# Thermocouple.net
KiCad netlist of a schematic drawn in EAGLE
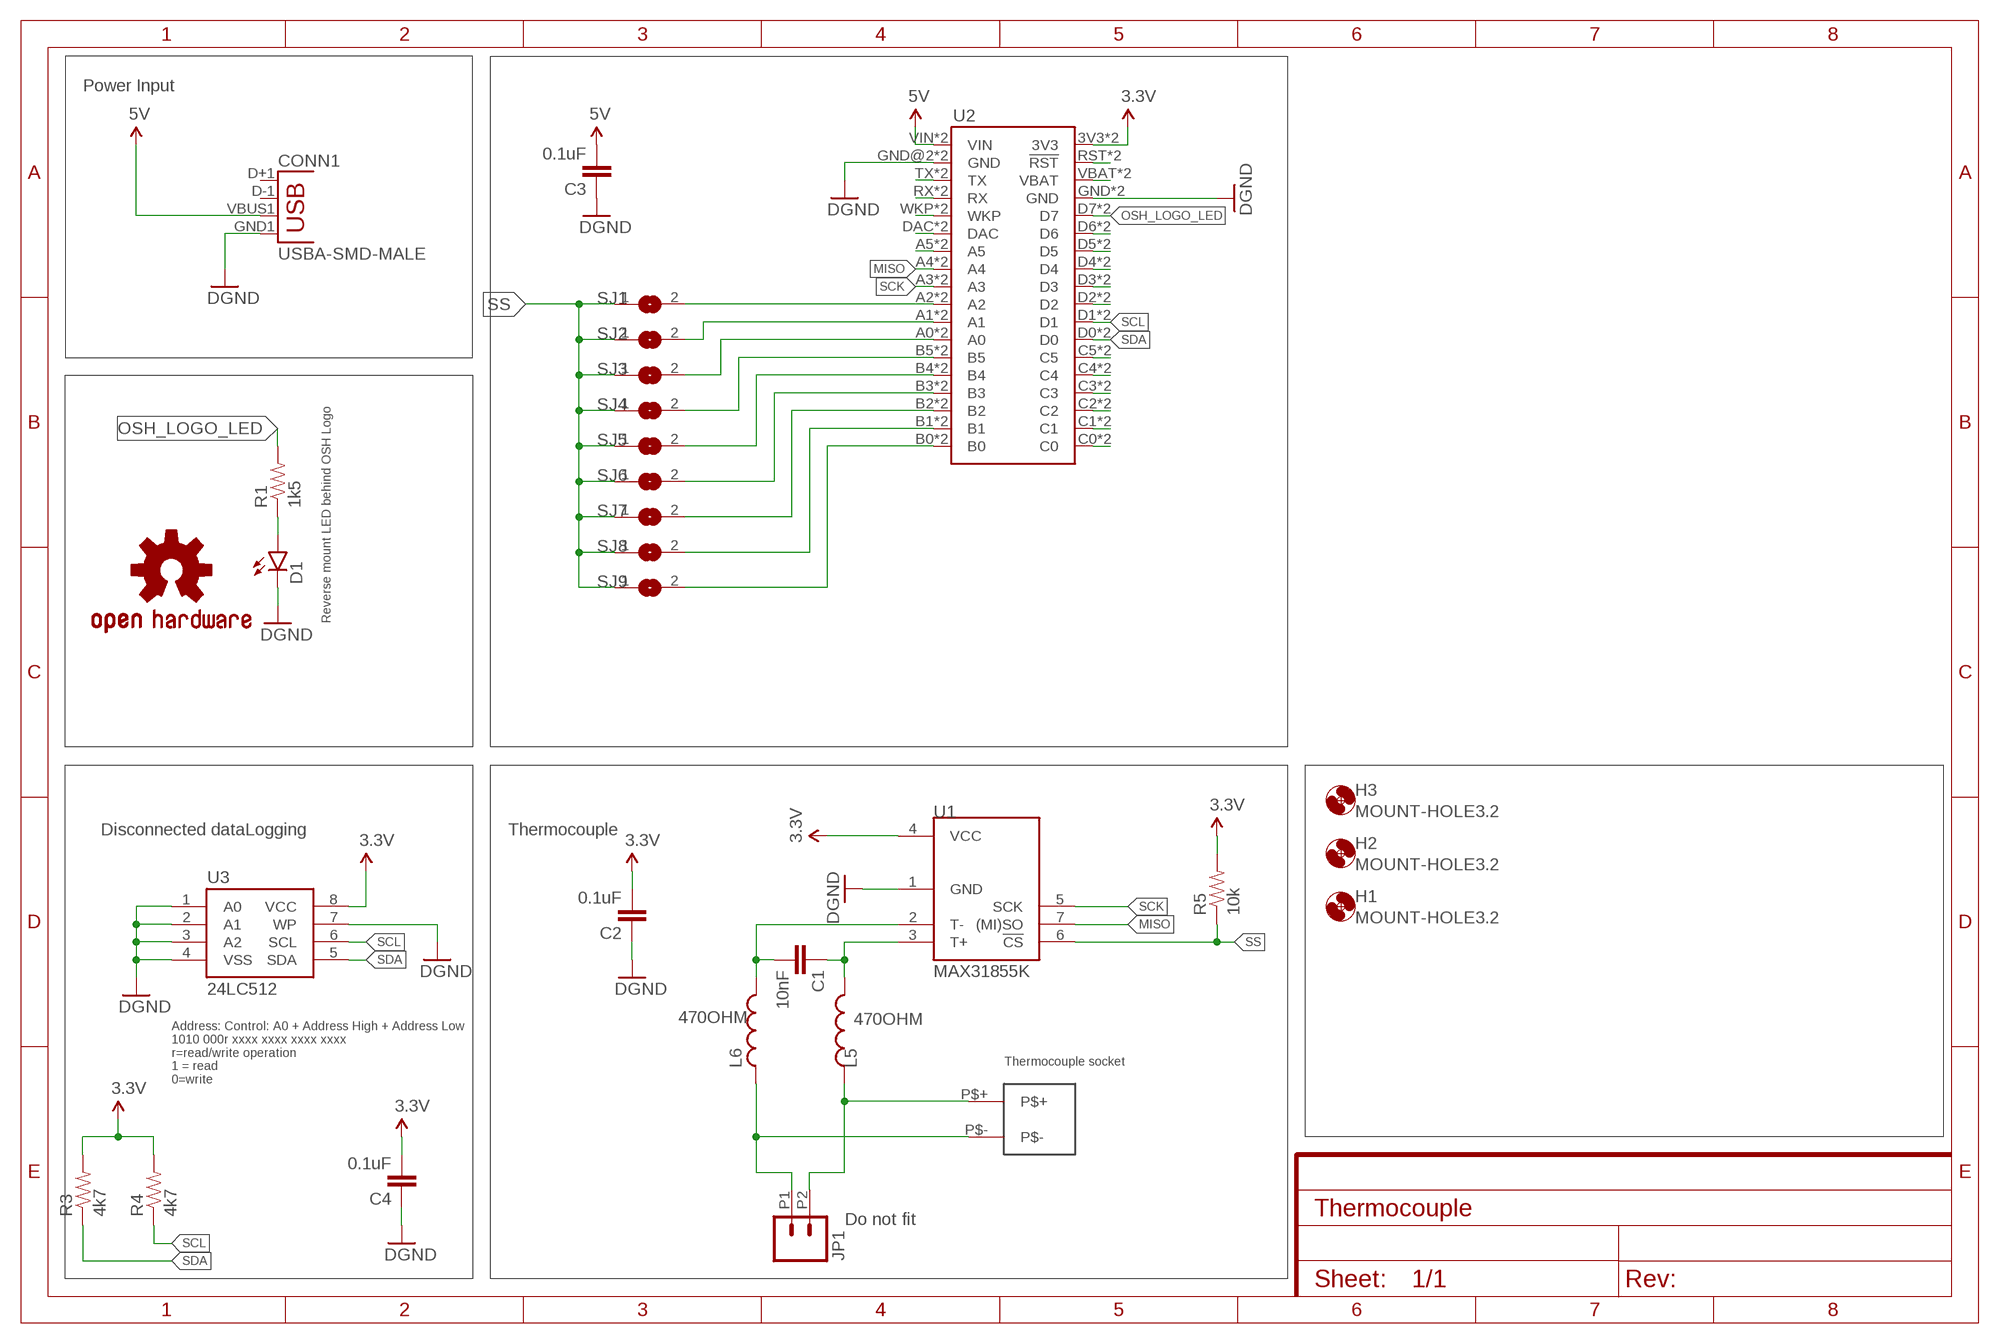
[diagram p0: schematic, sheet 1]

(export (version "E")
  (design (tool "Eeschema 10.0.6"))
  (components
    (comp (ref "C1")
      (value "10nF")
      (footprint "eagle-import:0805")
      (libsource (lib "eagle-import") (part "CAP0805"))
    )
    (comp (ref "C2")
      (value "0.1uF")
      (footprint "eagle-import:0805")
      (libsource (lib "eagle-import") (part "SparkFun-Passives_CAP0805"))
    )
    (comp (ref "C3")
      (value "0.1uF")
      (footprint "eagle-import:0805")
      (libsource (lib "eagle-import") (part "SparkFun-Passives_CAP0805"))
    )
    (comp (ref "C4")
      (value "0.1uF")
      (footprint "eagle-import:0805")
      (libsource (lib "eagle-import") (part "SparkFun-Passives_CAP0805"))
    )
    (comp (ref "CONN1")
      (value "USBA-SMD-MALE")
      (footprint "eagle-import:USB-A-SMT-MALE")
      (libsource (lib "eagle-import") (part "USBA-SMD-MALE"))
    )
    (comp (ref "D1")
      (value "LED1206-BOTTOM")
      (footprint "eagle-import:LED-1206-BOTTOM")
      (libsource (lib "eagle-import") (part "LED1206-BOTTOM"))
    )
    (comp (ref "H1")
      (value "MOUNT-HOLE3.2")
      (footprint "eagle-import:3,2")
      (libsource (lib "eagle-import") (part "MOUNT-HOLE3.2"))
    )
    (comp (ref "H2")
      (value "MOUNT-HOLE3.2")
      (footprint "eagle-import:3,2")
      (libsource (lib "eagle-import") (part "MOUNT-HOLE3.2"))
    )
    (comp (ref "H3")
      (value "MOUNT-HOLE3.2")
      (footprint "eagle-import:3,2")
      (libsource (lib "eagle-import") (part "MOUNT-HOLE3.2"))
    )
    (comp (ref "JP1")
      (value "M022.54MM_SCREWTERM")
      (footprint "eagle-import:1X02_2.54_SCREWTERM")
      (libsource (lib "eagle-import") (part "M022.54MM_SCREWTERM"))
    )
    (comp (ref "JP2")
      (value "THERMOCOUPLE_SOCKET_K-TYPE")
      (footprint "eagle-import:THERMOCOUPLE_SOCKET_K-TYPE")
      (libsource (lib "eagle-import") (part "THERMOCOUPLE_SOCKET_K-TYPE"))
    )
    (comp (ref "L5")
      (value "470OHM")
      (footprint "eagle-import:0805")
      (libsource (lib "eagle-import") (part "INDUCTOR0805"))
    )
    (comp (ref "L6")
      (value "470OHM")
      (footprint "eagle-import:0805")
      (libsource (lib "eagle-import") (part "INDUCTOR0805"))
    )
    (comp (ref "LOGO1")
      (value "OSHW-LOGOM")
      (footprint "eagle-import:OSHW-LOGO-M")
      (libsource (lib "eagle-import") (part "OSHW-LOGOM"))
    )
    (comp (ref "R1")
      (value "1k5")
      (footprint "eagle-import:1206")
      (libsource (lib "eagle-import") (part "RESISTOR1206"))
    )
    (comp (ref "R3")
      (value "4k7")
      (footprint "eagle-import:0805")
      (libsource (lib "eagle-import") (part "RESISTOR0805-RES"))
    )
    (comp (ref "R4")
      (value "4k7")
      (footprint "eagle-import:0805")
      (libsource (lib "eagle-import") (part "RESISTOR0805-RES"))
    )
    (comp (ref "R5")
      (value "10k")
      (footprint "eagle-import:0805")
      (libsource (lib "eagle-import") (part "RESISTOR0805-RES"))
    )
    (comp (ref "SJ1") (value "SJ") (footprint "eagle-import:SJ") (libsource (lib "eagle-import") (part "SJ")))
    (comp (ref "SJ2") (value "SJ") (footprint "eagle-import:SJ") (libsource (lib "eagle-import") (part "SJ")))
    (comp (ref "SJ3") (value "SJ") (footprint "eagle-import:SJ") (libsource (lib "eagle-import") (part "SJ")))
    (comp (ref "SJ4") (value "SJ") (footprint "eagle-import:SJ") (libsource (lib "eagle-import") (part "SJ")))
    (comp (ref "SJ5") (value "SJ") (footprint "eagle-import:SJ") (libsource (lib "eagle-import") (part "SJ")))
    (comp (ref "SJ6") (value "SJ") (footprint "eagle-import:SJ") (libsource (lib "eagle-import") (part "SJ")))
    (comp (ref "SJ7") (value "SJ") (footprint "eagle-import:SJ") (libsource (lib "eagle-import") (part "SJ")))
    (comp (ref "SJ8") (value "SJ") (footprint "eagle-import:SJ") (libsource (lib "eagle-import") (part "SJ")))
    (comp (ref "SJ9") (value "SJ") (footprint "eagle-import:SJ") (libsource (lib "eagle-import") (part "SJ")))
    (comp (ref "U1")
      (value "MAX31855K")
      (footprint "eagle-import:SOIC8")
      (libsource (lib "eagle-import") (part "MAX31855K"))
    )
    (comp (ref "U2")
      (value "ELECTRONDUALNAMED")
      (footprint "eagle-import:ELECTRON_SIMPLE_SILK_NAMES_DUAL")
      (libsource (lib "eagle-import") (part "ELECTRONDUALNAMED"))
    )
    (comp (ref "U3")
      (value "24LC512")
      (footprint "eagle-import:SO08")
      (libsource (lib "eagle-import") (part "EEPROM-I2CSMD"))
    )
  )
  (nets
    (net (code "1") (name "3.3V") (class "Default")
      (node (ref "C2") (pin "2") (pinfunction "2_2") (pintype "passive"))
      (node (ref "C4") (pin "2") (pinfunction "2_2") (pintype "passive"))
      (node (ref "R3") (pin "2") (pinfunction "2_2") (pintype "passive"))
      (node (ref "R4") (pin "2") (pinfunction "2_2") (pintype "passive"))
      (node (ref "R5") (pin "2") (pinfunction "2_2") (pintype "passive"))
      (node (ref "U1") (pin "4") (pinfunction "VCC_4") (pintype "bidirectional"))
      (node (ref "U2") (pin "3V3") (pinfunction "3V3_3V3") (pintype "power_in"))
      (node (ref "U2") (pin "3V3_1") (pinfunction "3V3_3V3_1") (pintype "power_in"))
      (node (ref "U3") (pin "8") (pinfunction "VCC_8") (pintype "power_in"))
    )
    (net (code "2") (name "5V") (class "Default")
      (node (ref "C3") (pin "2") (pinfunction "2_2") (pintype "passive"))
      (node (ref "CONN1") (pin "VBUS1") (pinfunction "VBUS_VBUS1") (pintype "bidirectional"))
      (node (ref "U2") (pin "VIN") (pinfunction "VIN_VIN") (pintype "power_in"))
      (node (ref "U2") (pin "VIN_1B") (pinfunction "VIN_VIN_1B") (pintype "power_in"))
    )
    (net (code "3") (name "DGND") (class "Default")
      (node (ref "C2") (pin "1") (pinfunction "1_1") (pintype "passive"))
      (node (ref "C3") (pin "1") (pinfunction "1_1") (pintype "passive"))
      (node (ref "C4") (pin "1") (pinfunction "1_1") (pintype "passive"))
      (node (ref "CONN1") (pin "GND1") (pinfunction "GND_GND1") (pintype "bidirectional"))
      (node (ref "D1") (pin "C") (pinfunction "C_C") (pintype "passive"))
      (node (ref "U1") (pin "1") (pinfunction "GND_1") (pintype "bidirectional"))
      (node (ref "U2") (pin "GND") (pinfunction "GND_GND") (pintype "power_in"))
      (node (ref "U2") (pin "GND@2") (pinfunction "GND_GND@2") (pintype "power_in"))
      (node (ref "U2") (pin "GND_1") (pinfunction "GND_GND_1") (pintype "power_in"))
      (node (ref "U2") (pin "GND_1B") (pinfunction "GND_GND_1B") (pintype "power_in"))
      (node (ref "U3") (pin "1") (pinfunction "A0_1") (pintype "bidirectional"))
      (node (ref "U3") (pin "2") (pinfunction "A1_2") (pintype "bidirectional"))
      (node (ref "U3") (pin "3") (pinfunction "A2_3") (pintype "bidirectional"))
      (node (ref "U3") (pin "4") (pinfunction "VSS_4") (pintype "power_in"))
      (node (ref "U3") (pin "7") (pinfunction "WP_7") (pintype "bidirectional"))
    )
    (net (code "4") (name "MISO") (class "Default")
      (node (ref "U1") (pin "7") (pinfunction "(MI)SO_7") (pintype "bidirectional"))
      (node (ref "U2") (pin "A4") (pinfunction "A4_A4") (pintype "bidirectional"))
      (node (ref "U2") (pin "A4_1") (pinfunction "A4_A4_1") (pintype "bidirectional"))
    )
    (net (code "5") (name "Net-(D1-PadA)") (class "Default")
      (node (ref "D1") (pin "A") (pinfunction "A_A") (pintype "passive"))
      (node (ref "R1") (pin "1") (pinfunction "1_1") (pintype "passive"))
    )
    (net (code "6") (name "Net-(JP1-1)") (class "Default")
      (node (ref "JP1") (pin "P1") (pinfunction "1_P1") (pintype "passive"))
      (node (ref "JP2") (pin "P$-") (pinfunction "P$-_P$-") (pintype "output"))
      (node (ref "L6") (pin "1") (pinfunction "1_1") (pintype "passive"))
    )
    (net (code "7") (name "Net-(JP1-2)") (class "Default")
      (node (ref "JP1") (pin "P2") (pinfunction "2_P2") (pintype "passive"))
      (node (ref "JP2") (pin "P$+") (pinfunction "P$+_P$+") (pintype "output"))
      (node (ref "L5") (pin "1") (pinfunction "1_1") (pintype "passive"))
    )
    (net (code "8") (name "Net-(SJ1-Pad2)") (class "Default")
      (node (ref "SJ1") (pin "2") (pinfunction "2_2") (pintype "passive"))
      (node (ref "U2") (pin "A2") (pinfunction "A2_A2") (pintype "bidirectional"))
      (node (ref "U2") (pin "A2_1") (pinfunction "A2_A2_1") (pintype "bidirectional"))
    )
    (net (code "9") (name "Net-(SJ2-Pad2)") (class "Default")
      (node (ref "SJ2") (pin "2") (pinfunction "2_2") (pintype "passive"))
      (node (ref "U2") (pin "A1") (pinfunction "A1_A1") (pintype "bidirectional"))
      (node (ref "U2") (pin "A1_1") (pinfunction "A1_A1_1") (pintype "bidirectional"))
    )
    (net (code "10") (name "Net-(SJ3-Pad2)") (class "Default")
      (node (ref "SJ3") (pin "2") (pinfunction "2_2") (pintype "passive"))
      (node (ref "U2") (pin "A0") (pinfunction "A0_A0") (pintype "bidirectional"))
      (node (ref "U2") (pin "A0_1") (pinfunction "A0_A0_1") (pintype "bidirectional"))
    )
    (net (code "11") (name "Net-(SJ4-Pad2)") (class "Default")
      (node (ref "SJ4") (pin "2") (pinfunction "2_2") (pintype "passive"))
      (node (ref "U2") (pin "B5") (pinfunction "B5_B5") (pintype "bidirectional"))
      (node (ref "U2") (pin "B5_1") (pinfunction "B5_B5_1") (pintype "bidirectional"))
    )
    (net (code "12") (name "Net-(SJ5-Pad2)") (class "Default")
      (node (ref "SJ5") (pin "2") (pinfunction "2_2") (pintype "passive"))
      (node (ref "U2") (pin "B4") (pinfunction "B4_B4") (pintype "bidirectional"))
      (node (ref "U2") (pin "B4_1") (pinfunction "B4_B4_1") (pintype "bidirectional"))
    )
    (net (code "13") (name "Net-(SJ6-Pad2)") (class "Default")
      (node (ref "SJ6") (pin "2") (pinfunction "2_2") (pintype "passive"))
      (node (ref "U2") (pin "B3") (pinfunction "B3_B3") (pintype "bidirectional"))
      (node (ref "U2") (pin "B3_1") (pinfunction "B3_B3_1") (pintype "bidirectional"))
    )
    (net (code "14") (name "Net-(SJ7-Pad2)") (class "Default")
      (node (ref "SJ7") (pin "2") (pinfunction "2_2") (pintype "passive"))
      (node (ref "U2") (pin "B2") (pinfunction "B2_B2") (pintype "bidirectional"))
      (node (ref "U2") (pin "B2_1") (pinfunction "B2_B2_1") (pintype "bidirectional"))
    )
    (net (code "15") (name "Net-(SJ8-Pad2)") (class "Default")
      (node (ref "SJ8") (pin "2") (pinfunction "2_2") (pintype "passive"))
      (node (ref "U2") (pin "B1") (pinfunction "B1_B1") (pintype "bidirectional"))
      (node (ref "U2") (pin "B1_1") (pinfunction "B1_B1_1") (pintype "bidirectional"))
    )
    (net (code "16") (name "Net-(SJ9-Pad2)") (class "Default")
      (node (ref "SJ9") (pin "2") (pinfunction "2_2") (pintype "passive"))
      (node (ref "U2") (pin "B0") (pinfunction "B0_B0") (pintype "bidirectional"))
      (node (ref "U2") (pin "B0_1") (pinfunction "B0_B0_1") (pintype "bidirectional"))
    )
    (net (code "17") (name "Net-(U1-T+)") (class "Default")
      (node (ref "C1") (pin "1") (pinfunction "1_1") (pintype "passive"))
      (node (ref "L5") (pin "2") (pinfunction "2_2") (pintype "passive"))
      (node (ref "U1") (pin "3") (pinfunction "T+_3") (pintype "bidirectional"))
    )
    (net (code "18") (name "Net-(U1-T-)") (class "Default")
      (node (ref "C1") (pin "2") (pinfunction "2_2") (pintype "passive"))
      (node (ref "L6") (pin "2") (pinfunction "2_2") (pintype "passive"))
      (node (ref "U1") (pin "2") (pinfunction "T-_2") (pintype "bidirectional"))
    )
    (net (code "19") (name "Net-(U2-A5-PadA5_1)") (class "Default")
      (node (ref "U2") (pin "A5") (pinfunction "A5_A5") (pintype "bidirectional"))
      (node (ref "U2") (pin "A5_1") (pinfunction "A5_A5_1") (pintype "bidirectional"))
    )
    (net (code "20") (name "Net-(U2-C0-PadC0_1)") (class "Default")
      (node (ref "U2") (pin "C0") (pinfunction "C0_C0") (pintype "bidirectional"))
      (node (ref "U2") (pin "C0_1") (pinfunction "C0_C0_1") (pintype "bidirectional"))
    )
    (net (code "21") (name "Net-(U2-C1-PadC1_1)") (class "Default")
      (node (ref "U2") (pin "C1") (pinfunction "C1_C1") (pintype "bidirectional"))
      (node (ref "U2") (pin "C1_1") (pinfunction "C1_C1_1") (pintype "bidirectional"))
    )
    (net (code "22") (name "Net-(U2-C2-PadC2_1)") (class "Default")
      (node (ref "U2") (pin "C2") (pinfunction "C2_C2") (pintype "bidirectional"))
      (node (ref "U2") (pin "C2_1") (pinfunction "C2_C2_1") (pintype "bidirectional"))
    )
    (net (code "23") (name "Net-(U2-C3-PadC3_1)") (class "Default")
      (node (ref "U2") (pin "C3") (pinfunction "C3_C3") (pintype "bidirectional"))
      (node (ref "U2") (pin "C3_1") (pinfunction "C3_C3_1") (pintype "bidirectional"))
    )
    (net (code "24") (name "Net-(U2-C4-PadC4_1)") (class "Default")
      (node (ref "U2") (pin "C4") (pinfunction "C4_C4") (pintype "bidirectional"))
      (node (ref "U2") (pin "C4_1") (pinfunction "C4_C4_1") (pintype "bidirectional"))
    )
    (net (code "25") (name "Net-(U2-C5-PadC5_1)") (class "Default")
      (node (ref "U2") (pin "C5") (pinfunction "C5_C5") (pintype "bidirectional"))
      (node (ref "U2") (pin "C5_1") (pinfunction "C5_C5_1") (pintype "bidirectional"))
    )
    (net (code "26") (name "Net-(U2-D2-PadD2_1)") (class "Default")
      (node (ref "U2") (pin "D2") (pinfunction "D2_D2") (pintype "bidirectional"))
      (node (ref "U2") (pin "D2_1") (pinfunction "D2_D2_1") (pintype "bidirectional"))
    )
    (net (code "27") (name "Net-(U2-D3-PadD3_1)") (class "Default")
      (node (ref "U2") (pin "D3") (pinfunction "D3_D3") (pintype "bidirectional"))
      (node (ref "U2") (pin "D3_1") (pinfunction "D3_D3_1") (pintype "bidirectional"))
    )
    (net (code "28") (name "Net-(U2-D4-PadD4_1)") (class "Default")
      (node (ref "U2") (pin "D4") (pinfunction "D4_D4") (pintype "bidirectional"))
      (node (ref "U2") (pin "D4_1") (pinfunction "D4_D4_1") (pintype "bidirectional"))
    )
    (net (code "29") (name "Net-(U2-D5-PadD5_1)") (class "Default")
      (node (ref "U2") (pin "D5") (pinfunction "D5_D5") (pintype "bidirectional"))
      (node (ref "U2") (pin "D5_1") (pinfunction "D5_D5_1") (pintype "bidirectional"))
    )
    (net (code "30") (name "Net-(U2-D6-PadD6_1)") (class "Default")
      (node (ref "U2") (pin "D6") (pinfunction "D6_D6") (pintype "bidirectional"))
      (node (ref "U2") (pin "D6_1") (pinfunction "D6_D6_1") (pintype "bidirectional"))
    )
    (net (code "31") (name "Net-(U2-DAC-PadDAC_1)") (class "Default")
      (node (ref "U2") (pin "DAC") (pinfunction "DAC_DAC") (pintype "bidirectional"))
      (node (ref "U2") (pin "DAC_1") (pinfunction "DAC_DAC_1") (pintype "bidirectional"))
    )
    (net (code "32") (name "Net-(U2-PadRX)") (class "Default")
      (node (ref "U2") (pin "RX") (pinfunction "RX_RX") (pintype "bidirectional"))
      (node (ref "U2") (pin "RX_1") (pinfunction "RX_RX_1") (pintype "bidirectional"))
    )
    (net (code "33") (name "Net-(U2-PadTX)") (class "Default")
      (node (ref "U2") (pin "TX") (pinfunction "TX_TX") (pintype "bidirectional"))
      (node (ref "U2") (pin "TX_1") (pinfunction "TX_TX_1") (pintype "bidirectional"))
    )
    (net (code "34") (name "Net-(U2-PadVBAT)") (class "Default")
      (node (ref "U2") (pin "VBAT") (pinfunction "VBAT_VBAT") (pintype "passive"))
      (node (ref "U2") (pin "VBATT_1") (pinfunction "VBAT_VBATT_1") (pintype "passive"))
    )
    (net (code "35") (name "Net-(U2-PadWKP)") (class "Default")
      (node (ref "U2") (pin "WKP") (pinfunction "WKP_WKP") (pintype "bidirectional"))
      (node (ref "U2") (pin "WKP_1") (pinfunction "WKP_WKP_1") (pintype "bidirectional"))
    )
    (net (code "36") (name "Net-(U2-~{RST}-PadRST)") (class "Default")
      (node (ref "U2") (pin "RST") (pinfunction "~{RST}_RST") (pintype "bidirectional"))
      (node (ref "U2") (pin "RST_1") (pinfunction "~{RST}_RST_1") (pintype "bidirectional"))
    )
    (net (code "37") (name "OSH_LOGO_LED") (class "Default")
      (node (ref "R1") (pin "2") (pinfunction "2_2") (pintype "passive"))
      (node (ref "U2") (pin "D7") (pinfunction "D7_D7") (pintype "bidirectional"))
      (node (ref "U2") (pin "D7_1") (pinfunction "D7_D7_1") (pintype "bidirectional"))
    )
    (net (code "38") (name "SCK") (class "Default")
      (node (ref "U1") (pin "5") (pinfunction "SCK_5") (pintype "bidirectional"))
      (node (ref "U2") (pin "A3") (pinfunction "A3_A3") (pintype "bidirectional"))
      (node (ref "U2") (pin "A3_1") (pinfunction "A3_A3_1") (pintype "bidirectional"))
    )
    (net (code "39") (name "SCL") (class "Default")
      (node (ref "R4") (pin "1") (pinfunction "1_1") (pintype "passive"))
      (node (ref "U2") (pin "D1") (pinfunction "D1_D1") (pintype "bidirectional"))
      (node (ref "U2") (pin "D1_1") (pinfunction "D1_D1_1") (pintype "bidirectional"))
      (node (ref "U3") (pin "6") (pinfunction "SCL_6") (pintype "bidirectional"))
    )
    (net (code "40") (name "SDA") (class "Default")
      (node (ref "R3") (pin "1") (pinfunction "1_1") (pintype "passive"))
      (node (ref "U2") (pin "D0") (pinfunction "D0_D0") (pintype "bidirectional"))
      (node (ref "U2") (pin "D0_1") (pinfunction "D0_D0_1") (pintype "bidirectional"))
      (node (ref "U3") (pin "5") (pinfunction "SDA_5") (pintype "bidirectional"))
    )
    (net (code "41") (name "SS") (class "Default")
      (node (ref "R5") (pin "1") (pinfunction "1_1") (pintype "passive"))
      (node (ref "SJ1") (pin "1") (pinfunction "1_1") (pintype "passive"))
      (node (ref "SJ2") (pin "1") (pinfunction "1_1") (pintype "passive"))
      (node (ref "SJ3") (pin "1") (pinfunction "1_1") (pintype "passive"))
      (node (ref "SJ4") (pin "1") (pinfunction "1_1") (pintype "passive"))
      (node (ref "SJ5") (pin "1") (pinfunction "1_1") (pintype "passive"))
      (node (ref "SJ6") (pin "1") (pinfunction "1_1") (pintype "passive"))
      (node (ref "SJ7") (pin "1") (pinfunction "1_1") (pintype "passive"))
      (node (ref "SJ8") (pin "1") (pinfunction "1_1") (pintype "passive"))
      (node (ref "SJ9") (pin "1") (pinfunction "1_1") (pintype "passive"))
      (node (ref "U1") (pin "6") (pinfunction "~{CS}_6") (pintype "bidirectional"))
    )
    (net (code "42") (name "unconnected-(CONN1-D+-PadD+1)") (class "Default")
      (node (ref "CONN1") (pin "D+1") (pinfunction "D+_D+1") (pintype "bidirectional"))
    )
    (net (code "43") (name "unconnected-(CONN1-D--PadD-1)") (class "Default")
      (node (ref "CONN1") (pin "D-1") (pinfunction "D-_D-1") (pintype "bidirectional"))
    )
  )
)
